# MT9V024.net
KiCad netlist of a schematic drawn in EAGLE
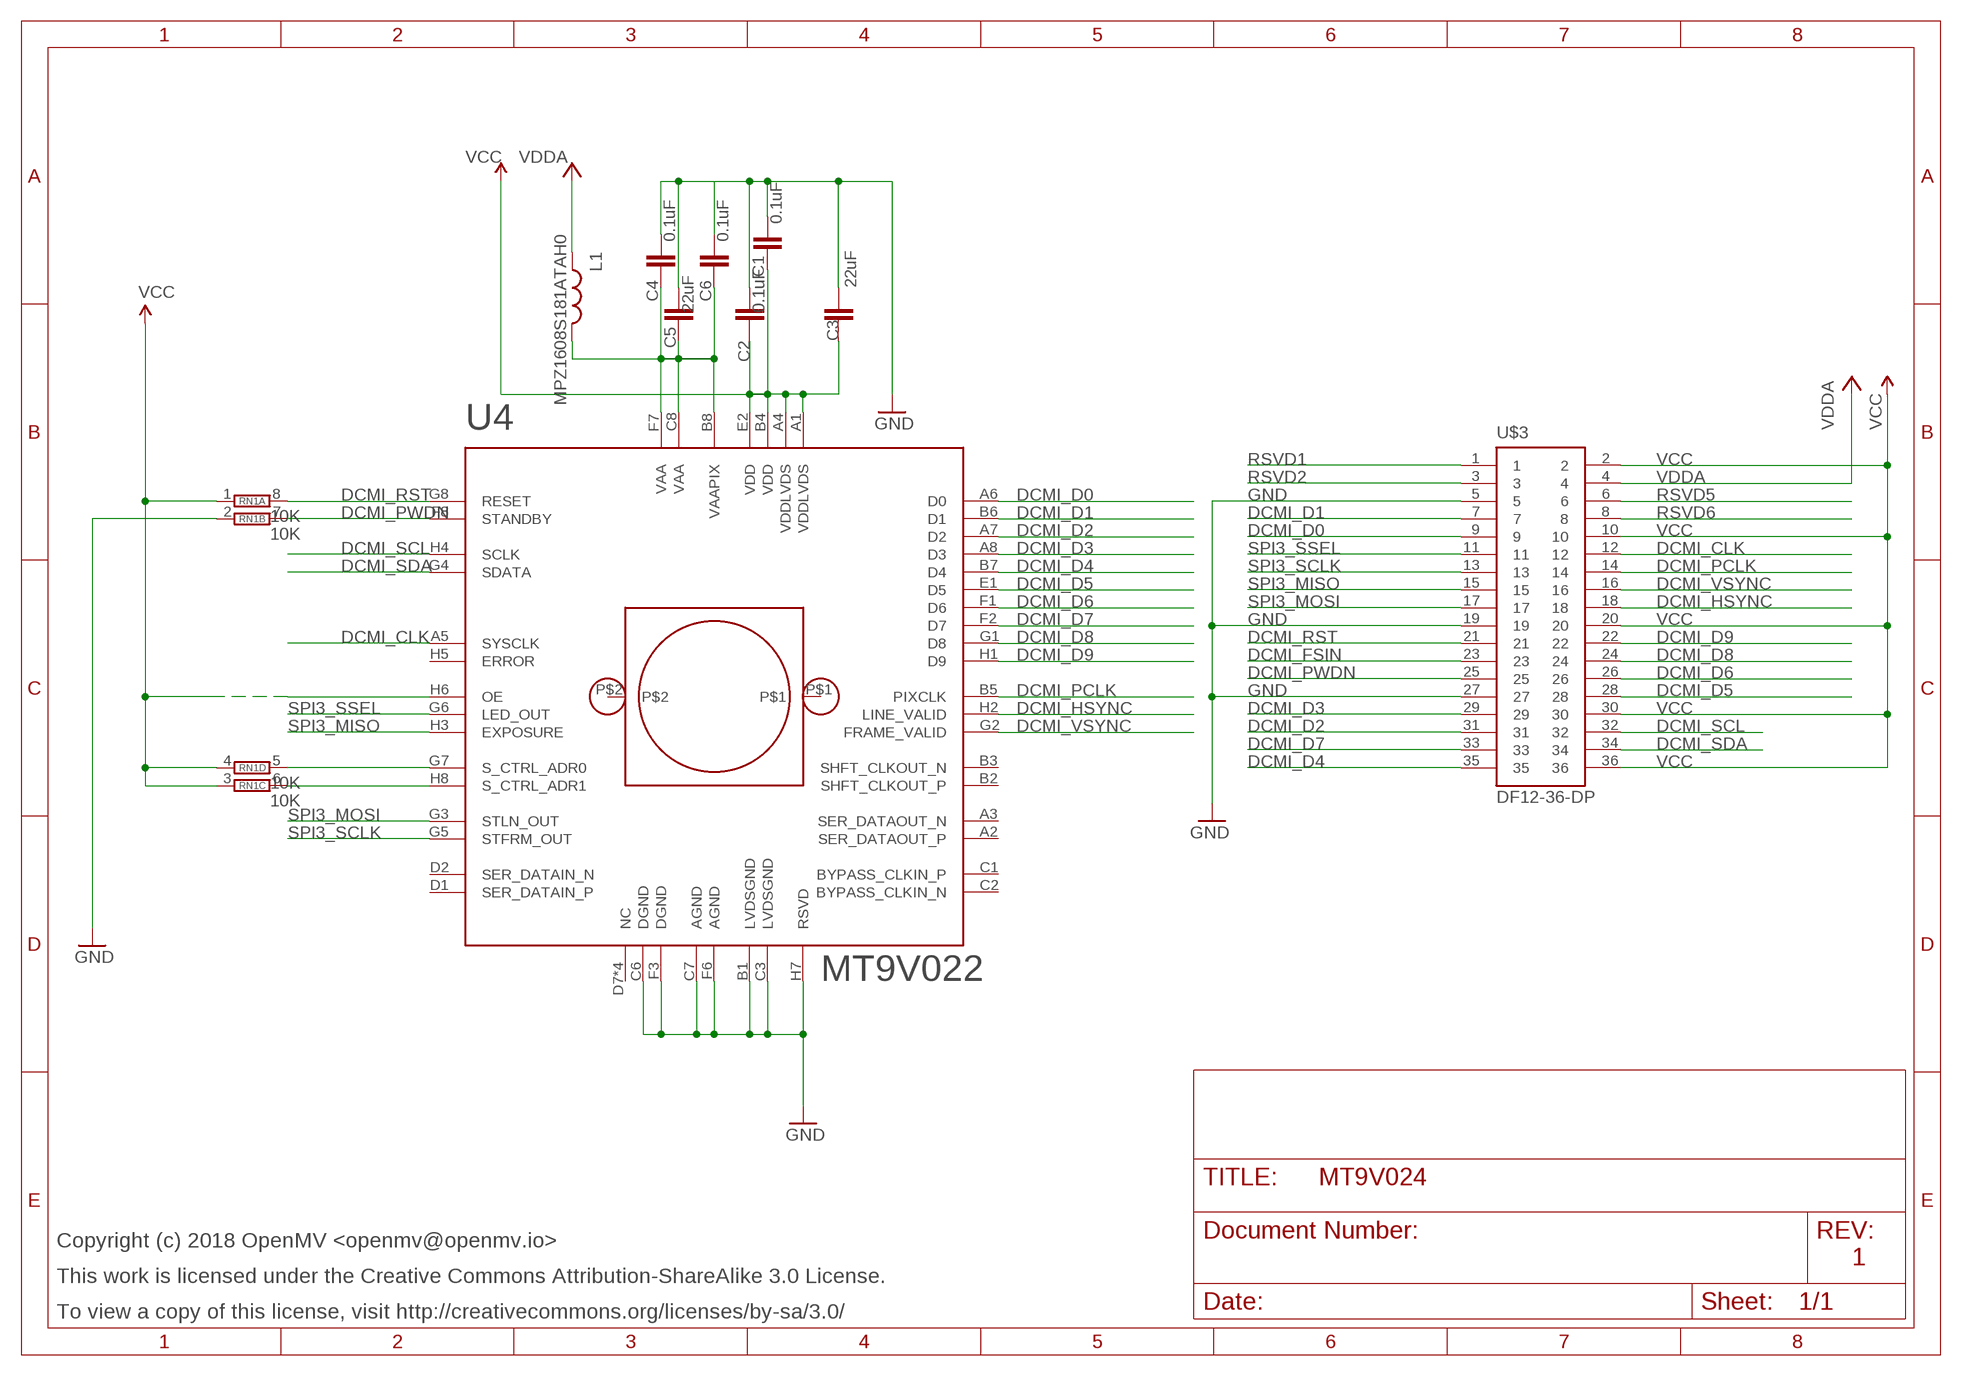
[diagram p0: schematic, sheet 1]

(export (version "E")
  (design (tool "Eeschema 10.0.6"))
  (components
    (comp (ref "C1")
      (value "0.1uF")
      (footprint "eagle-import:0402-CAP")
      (libsource (lib "eagle-import") (part "CAP0402-CAP"))
    )
    (comp (ref "C2")
      (value "0.1uF")
      (footprint "eagle-import:0402-CAP")
      (libsource (lib "eagle-import") (part "CAP0402-CAP"))
    )
    (comp (ref "C3")
      (value "22uF")
      (footprint "eagle-import:0805")
      (libsource (lib "eagle-import") (part "CAP0805"))
    )
    (comp (ref "C4")
      (value "0.1uF")
      (footprint "eagle-import:0402-CAP")
      (libsource (lib "eagle-import") (part "CAP0402-CAP"))
    )
    (comp (ref "C5")
      (value "22uF")
      (footprint "eagle-import:0805")
      (libsource (lib "eagle-import") (part "CAP0805"))
    )
    (comp (ref "C6")
      (value "0.1uF")
      (footprint "eagle-import:0402-CAP")
      (libsource (lib "eagle-import") (part "CAP0402-CAP"))
    )
    (comp (ref "L1")
      (value "MPZ1608S181ATAH0")
      (footprint "eagle-import:0603")
      (libsource (lib "eagle-import") (part "INDUCTOR0603"))
    )
    (comp (ref "LM1")
      (value "LENSMOUNT20MM")
      (footprint "eagle-import:LENSMOUNT-20MM")
      (libsource (lib "eagle-import") (part "LENSMOUNT20MM"))
    )
    (comp (ref "RN1")
      (value "10K")
      (footprint "eagle-import:EXBV8V")
      (fields (field (name "OC_FARNELL") "unknown") (field (name "OC_NEWARK") "unknown"))
      (libsource (lib "eagle-import") (part "4R-NEXBV8V"))
    )
    (comp (ref "U$3")
      (value "DF12-36-DP")
      (footprint "eagle-import:DF12-36-DP")
      (libsource (lib "eagle-import") (part "DF12-36-DP"))
    )
    (comp (ref "U4")
      (value "MT9V022")
      (footprint "eagle-import:IBGA52")
      (libsource (lib "eagle-import") (part "MT9V022"))
    )
  )
  (nets
    (net (code "1") (name "/DCMI_CLK") (class "Default")
      (node (ref "U$3") (pin "12") (pinfunction "12_12") (pintype "bidirectional"))
      (node (ref "U4") (pin "A5") (pinfunction "SYSCLK_A5") (pintype "bidirectional"))
    )
    (net (code "2") (name "/DCMI_D0") (class "Default")
      (node (ref "U$3") (pin "9") (pinfunction "9_9") (pintype "bidirectional"))
      (node (ref "U4") (pin "A6") (pinfunction "D0_A6") (pintype "bidirectional"))
    )
    (net (code "3") (name "/DCMI_D1") (class "Default")
      (node (ref "U$3") (pin "7") (pinfunction "7_7") (pintype "bidirectional"))
      (node (ref "U4") (pin "B6") (pinfunction "D1_B6") (pintype "bidirectional"))
    )
    (net (code "4") (name "/DCMI_D2") (class "Default")
      (node (ref "U$3") (pin "31") (pinfunction "31_31") (pintype "bidirectional"))
      (node (ref "U4") (pin "A7") (pinfunction "D2_A7") (pintype "bidirectional"))
    )
    (net (code "5") (name "/DCMI_D3") (class "Default")
      (node (ref "U$3") (pin "29") (pinfunction "29_29") (pintype "bidirectional"))
      (node (ref "U4") (pin "A8") (pinfunction "D3_A8") (pintype "bidirectional"))
    )
    (net (code "6") (name "/DCMI_D4") (class "Default")
      (node (ref "U$3") (pin "35") (pinfunction "35_35") (pintype "bidirectional"))
      (node (ref "U4") (pin "B7") (pinfunction "D4_B7") (pintype "bidirectional"))
    )
    (net (code "7") (name "/DCMI_D5") (class "Default")
      (node (ref "U$3") (pin "28") (pinfunction "28_28") (pintype "bidirectional"))
      (node (ref "U4") (pin "E1") (pinfunction "D5_E1") (pintype "bidirectional"))
    )
    (net (code "8") (name "/DCMI_D6") (class "Default")
      (node (ref "U$3") (pin "26") (pinfunction "26_26") (pintype "bidirectional"))
      (node (ref "U4") (pin "F1") (pinfunction "D6_F1") (pintype "bidirectional"))
    )
    (net (code "9") (name "/DCMI_D7") (class "Default")
      (node (ref "U$3") (pin "33") (pinfunction "33_33") (pintype "bidirectional"))
      (node (ref "U4") (pin "F2") (pinfunction "D7_F2") (pintype "bidirectional"))
    )
    (net (code "10") (name "/DCMI_D8") (class "Default")
      (node (ref "U$3") (pin "24") (pinfunction "24_24") (pintype "bidirectional"))
      (node (ref "U4") (pin "G1") (pinfunction "D8_G1") (pintype "bidirectional"))
    )
    (net (code "11") (name "/DCMI_D9") (class "Default")
      (node (ref "U$3") (pin "22") (pinfunction "22_22") (pintype "bidirectional"))
      (node (ref "U4") (pin "H1") (pinfunction "D9_H1") (pintype "bidirectional"))
    )
    (net (code "12") (name "/DCMI_FSIN") (class "Default")
      (node (ref "U$3") (pin "23") (pinfunction "23_23") (pintype "bidirectional"))
    )
    (net (code "13") (name "/DCMI_HSYNC") (class "Default")
      (node (ref "U$3") (pin "18") (pinfunction "18_18") (pintype "bidirectional"))
      (node (ref "U4") (pin "H2") (pinfunction "LINE_VALID_H2") (pintype "bidirectional"))
    )
    (net (code "14") (name "/DCMI_PCLK") (class "Default")
      (node (ref "U$3") (pin "14") (pinfunction "14_14") (pintype "bidirectional"))
      (node (ref "U4") (pin "B5") (pinfunction "PIXCLK_B5") (pintype "bidirectional"))
    )
    (net (code "15") (name "/DCMI_PWDN") (class "Default")
      (node (ref "RN1") (pin "7") (pinfunction "2_7") (pintype "passive"))
      (node (ref "U$3") (pin "25") (pinfunction "25_25") (pintype "bidirectional"))
      (node (ref "U4") (pin "F8") (pinfunction "STANDBY_F8") (pintype "bidirectional"))
    )
    (net (code "16") (name "/DCMI_RST") (class "Default")
      (node (ref "RN1") (pin "8") (pinfunction "2_8") (pintype "passive"))
      (node (ref "U$3") (pin "21") (pinfunction "21_21") (pintype "bidirectional"))
      (node (ref "U4") (pin "G8") (pinfunction "RESET_G8") (pintype "bidirectional"))
    )
    (net (code "17") (name "/DCMI_SCL") (class "Default")
      (node (ref "U$3") (pin "32") (pinfunction "32_32") (pintype "bidirectional"))
      (node (ref "U4") (pin "H4") (pinfunction "SCLK_H4") (pintype "bidirectional"))
    )
    (net (code "18") (name "/DCMI_SDA") (class "Default")
      (node (ref "U$3") (pin "34") (pinfunction "34_34") (pintype "bidirectional"))
      (node (ref "U4") (pin "G4") (pinfunction "SDATA_G4") (pintype "bidirectional"))
    )
    (net (code "19") (name "/DCMI_VSYNC") (class "Default")
      (node (ref "U$3") (pin "16") (pinfunction "16_16") (pintype "bidirectional"))
      (node (ref "U4") (pin "G2") (pinfunction "FRAME_VALID_G2") (pintype "bidirectional"))
    )
    (net (code "20") (name "/P$1") (class "Default")
      (node (ref "LM1") (pin "P$1") (pinfunction "P$1_P$1") (pintype "power_in"))
    )
    (net (code "21") (name "/P$2") (class "Default")
      (node (ref "LM1") (pin "P$2") (pinfunction "P$2_P$2") (pintype "power_in"))
    )
    (net (code "22") (name "/RSVD1") (class "Default")
      (node (ref "U$3") (pin "1") (pinfunction "1_1") (pintype "bidirectional"))
    )
    (net (code "23") (name "/RSVD2") (class "Default")
      (node (ref "U$3") (pin "3") (pinfunction "3_3") (pintype "bidirectional"))
    )
    (net (code "24") (name "/RSVD5") (class "Default")
      (node (ref "U$3") (pin "6") (pinfunction "6_6") (pintype "bidirectional"))
    )
    (net (code "25") (name "/RSVD6") (class "Default")
      (node (ref "U$3") (pin "8") (pinfunction "8_8") (pintype "bidirectional"))
    )
    (net (code "26") (name "/SPI3_MISO") (class "Default")
      (node (ref "U$3") (pin "15") (pinfunction "15_15") (pintype "bidirectional"))
      (node (ref "U4") (pin "H3") (pinfunction "EXPOSURE_H3") (pintype "bidirectional"))
    )
    (net (code "27") (name "/SPI3_MOSI") (class "Default")
      (node (ref "U$3") (pin "17") (pinfunction "17_17") (pintype "bidirectional"))
      (node (ref "U4") (pin "G3") (pinfunction "STLN_OUT_G3") (pintype "bidirectional"))
    )
    (net (code "28") (name "/SPI3_SCLK") (class "Default")
      (node (ref "U$3") (pin "13") (pinfunction "13_13") (pintype "bidirectional"))
      (node (ref "U4") (pin "G5") (pinfunction "STFRM_OUT_G5") (pintype "bidirectional"))
    )
    (net (code "29") (name "/SPI3_SSEL") (class "Default")
      (node (ref "U$3") (pin "11") (pinfunction "11_11") (pintype "bidirectional"))
      (node (ref "U4") (pin "G6") (pinfunction "LED_OUT_G6") (pintype "bidirectional"))
    )
    (net (code "30") (name "GND") (class "Default")
      (node (ref "C1") (pin "2") (pinfunction "2_2") (pintype "passive"))
      (node (ref "C2") (pin "2") (pinfunction "2_2") (pintype "passive"))
      (node (ref "C3") (pin "1") (pinfunction "1_1") (pintype "passive"))
      (node (ref "C4") (pin "2") (pinfunction "2_2") (pintype "passive"))
      (node (ref "C5") (pin "1") (pinfunction "1_1") (pintype "passive"))
      (node (ref "C6") (pin "2") (pinfunction "2_2") (pintype "passive"))
      (node (ref "RN1") (pin "2") (pinfunction "1_2") (pintype "passive"))
      (node (ref "U$3") (pin "19") (pinfunction "19_19") (pintype "bidirectional"))
      (node (ref "U$3") (pin "27") (pinfunction "27_27") (pintype "bidirectional"))
      (node (ref "U$3") (pin "5") (pinfunction "5_5") (pintype "bidirectional"))
      (node (ref "U4") (pin "B1") (pinfunction "LVDSGND_B1") (pintype "power_in"))
      (node (ref "U4") (pin "C3") (pinfunction "LVDSGND_C3") (pintype "power_in"))
      (node (ref "U4") (pin "C6") (pinfunction "DGND_C6") (pintype "power_in"))
      (node (ref "U4") (pin "C7") (pinfunction "AGND_C7") (pintype "power_in"))
      (node (ref "U4") (pin "F3") (pinfunction "DGND_F3") (pintype "power_in"))
      (node (ref "U4") (pin "F6") (pinfunction "AGND_F6") (pintype "power_in"))
      (node (ref "U4") (pin "H7") (pinfunction "RSVD_H7") (pintype "power_in"))
    )
    (net (code "31") (name "Net-(RN1C-2)") (class "Default")
      (node (ref "RN1") (pin "6") (pinfunction "2_6") (pintype "passive"))
      (node (ref "U4") (pin "H8") (pinfunction "S_CTRL_ADR1_H8") (pintype "bidirectional"))
    )
    (net (code "32") (name "Net-(RN1D-2)") (class "Default")
      (node (ref "RN1") (pin "5") (pinfunction "2_5") (pintype "passive"))
      (node (ref "U4") (pin "G7") (pinfunction "S_CTRL_ADR0_G7") (pintype "bidirectional"))
    )
    (net (code "33") (name "Net-(U4-VAAPIX)") (class "Default")
      (node (ref "C4") (pin "1") (pinfunction "1_1") (pintype "passive"))
      (node (ref "C5") (pin "2") (pinfunction "2_2") (pintype "passive"))
      (node (ref "C6") (pin "1") (pinfunction "1_1") (pintype "passive"))
      (node (ref "L1") (pin "2") (pinfunction "2_2") (pintype "passive"))
      (node (ref "U4") (pin "B8") (pinfunction "VAAPIX_B8") (pintype "power_in"))
      (node (ref "U4") (pin "C8") (pinfunction "VAA_C8") (pintype "power_in"))
      (node (ref "U4") (pin "F7") (pinfunction "VAA_F7") (pintype "power_in"))
    )
    (net (code "34") (name "VCC") (class "Default")
      (node (ref "C1") (pin "1") (pinfunction "1_1") (pintype "passive"))
      (node (ref "C2") (pin "1") (pinfunction "1_1") (pintype "passive"))
      (node (ref "C3") (pin "2") (pinfunction "2_2") (pintype "passive"))
      (node (ref "RN1") (pin "1") (pinfunction "1_1") (pintype "passive"))
      (node (ref "RN1") (pin "3") (pinfunction "1_3") (pintype "passive"))
      (node (ref "RN1") (pin "4") (pinfunction "1_4") (pintype "passive"))
      (node (ref "U$3") (pin "10") (pinfunction "10_10") (pintype "bidirectional"))
      (node (ref "U$3") (pin "2") (pinfunction "2_2") (pintype "bidirectional"))
      (node (ref "U$3") (pin "20") (pinfunction "20_20") (pintype "bidirectional"))
      (node (ref "U$3") (pin "30") (pinfunction "30_30") (pintype "bidirectional"))
      (node (ref "U$3") (pin "36") (pinfunction "36_36") (pintype "bidirectional"))
      (node (ref "U4") (pin "A1") (pinfunction "VDDLVDS_A1") (pintype "passive"))
      (node (ref "U4") (pin "A4") (pinfunction "VDDLVDS_A4") (pintype "passive"))
      (node (ref "U4") (pin "B4") (pinfunction "VDD_B4") (pintype "power_in"))
      (node (ref "U4") (pin "E2") (pinfunction "VDD_E2") (pintype "power_in"))
      (node (ref "U4") (pin "H6") (pinfunction "OE_H6") (pintype "bidirectional"))
    )
    (net (code "35") (name "VDDA") (class "Default")
      (node (ref "L1") (pin "1") (pinfunction "1_1") (pintype "passive"))
      (node (ref "U$3") (pin "4") (pinfunction "4_4") (pintype "bidirectional"))
    )
    (net (code "36") (name "unconnected-(U4-BYPASS_CLKIN_N-PadC2)") (class "Default")
      (node (ref "U4") (pin "C2") (pinfunction "BYPASS_CLKIN_N_C2") (pintype "bidirectional"))
    )
    (net (code "37") (name "unconnected-(U4-BYPASS_CLKIN_P-PadC1)") (class "Default")
      (node (ref "U4") (pin "C1") (pinfunction "BYPASS_CLKIN_P_C1") (pintype "bidirectional"))
    )
    (net (code "38") (name "unconnected-(U4-ERROR-PadH5)") (class "Default")
      (node (ref "U4") (pin "H5") (pinfunction "ERROR_H5") (pintype "bidirectional"))
    )
    (net (code "39") (name "unconnected-(U4-NC-PadD7)") (class "Default")
      (node (ref "U4") (pin "D7") (pinfunction "NC_D7") (pintype "no_connect"))
    )
    (net (code "40") (name "unconnected-(U4-NC-PadD8)") (class "Default")
      (node (ref "U4") (pin "D8") (pinfunction "NC_D8") (pintype "no_connect"))
    )
    (net (code "41") (name "unconnected-(U4-NC-PadE7)") (class "Default")
      (node (ref "U4") (pin "E7") (pinfunction "NC_E7") (pintype "no_connect"))
    )
    (net (code "42") (name "unconnected-(U4-NC-PadE8)") (class "Default")
      (node (ref "U4") (pin "E8") (pinfunction "NC_E8") (pintype "no_connect"))
    )
    (net (code "43") (name "unconnected-(U4-SER_DATAIN_N-PadD2)") (class "Default")
      (node (ref "U4") (pin "D2") (pinfunction "SER_DATAIN_N_D2") (pintype "bidirectional"))
    )
    (net (code "44") (name "unconnected-(U4-SER_DATAIN_P-PadD1)") (class "Default")
      (node (ref "U4") (pin "D1") (pinfunction "SER_DATAIN_P_D1") (pintype "bidirectional"))
    )
    (net (code "45") (name "unconnected-(U4-SER_DATAOUT_N-PadA3)") (class "Default")
      (node (ref "U4") (pin "A3") (pinfunction "SER_DATAOUT_N_A3") (pintype "bidirectional"))
    )
    (net (code "46") (name "unconnected-(U4-SER_DATAOUT_P-PadA2)") (class "Default")
      (node (ref "U4") (pin "A2") (pinfunction "SER_DATAOUT_P_A2") (pintype "bidirectional"))
    )
    (net (code "47") (name "unconnected-(U4-SHFT_CLKOUT_N-PadB3)") (class "Default")
      (node (ref "U4") (pin "B3") (pinfunction "SHFT_CLKOUT_N_B3") (pintype "bidirectional"))
    )
    (net (code "48") (name "unconnected-(U4-SHFT_CLKOUT_P-PadB2)") (class "Default")
      (node (ref "U4") (pin "B2") (pinfunction "SHFT_CLKOUT_P_B2") (pintype "bidirectional"))
    )
  )
)
